# HarmonicControl.net
KiCad netlist of a schematic drawn in Altium Designer
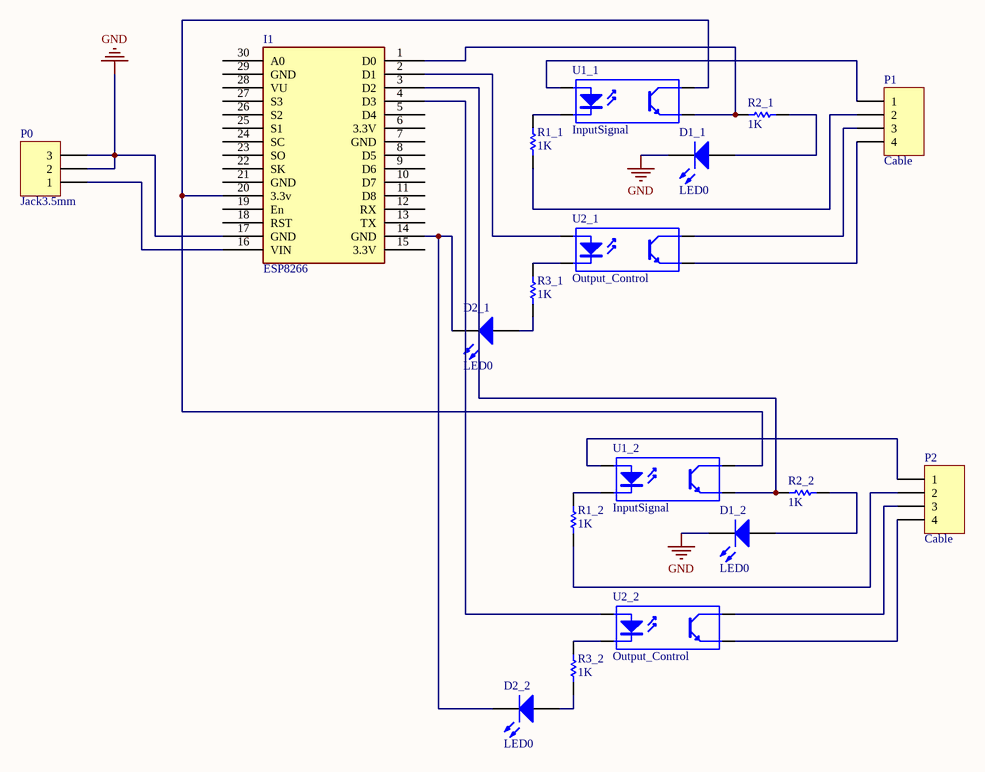
[diagram p0: HarmonicControl.SchDoc]

(export (version "E")
  (design (tool "Eeschema 10.0.6"))
  (components
    (comp (ref "D1_1")
      (value "LED0")
      (footprint "LED-0")
      (description "Typical INFRARED GaAs LED")
      (fields (field (name "PUBLISHER") "Altium Limited"))
      (libsource (lib "Miscellaneous Devices") (part "LED0"))
    )
    (comp (ref "D1_2")
      (value "LED0")
      (footprint "LED-0")
      (description "Typical INFRARED GaAs LED")
      (fields (field (name "PUBLISHER") "Altium Limited"))
      (libsource (lib "Miscellaneous Devices") (part "LED0"))
    )
    (comp (ref "D2_1")
      (value "LED0")
      (footprint "LED-0")
      (description "Typical INFRARED GaAs LED")
      (fields (field (name "PUBLISHER") "Altium Limited"))
      (libsource (lib "Miscellaneous Devices") (part "LED0"))
    )
    (comp (ref "D2_2")
      (value "LED0")
      (footprint "LED-0")
      (description "Typical INFRARED GaAs LED")
      (fields (field (name "PUBLISHER") "Altium Limited"))
      (libsource (lib "Miscellaneous Devices") (part "LED0"))
    )
    (comp (ref "I1")
      (value "ESP8266")
      (footprint "ESP8266_Node_MCU_V3")
      (libsource (lib "ESP8266_NodeMCU_12F_V3") (part "ESP8266_Node_MCU_V3"))
    )
    (comp (ref "P0")
      (value "Jack3.5mm")
      (footprint "HDR1X3")
      (description "Header, 3-Pin")
      (fields (field (name "PUBLISHER") "Altium Limited"))
      (libsource (lib "Miscellaneous Connectors") (part "Header 3"))
    )
    (comp (ref "P1")
      (value "Cable")
      (footprint "HDR1X4")
      (description "Header, 4-Pin")
      (fields (field (name "PUBLISHER") "Altium Limited"))
      (libsource (lib "Miscellaneous Connectors") (part "Header 4"))
    )
    (comp (ref "P2")
      (value "Cable")
      (footprint "HDR1X4")
      (description "Header, 4-Pin")
      (fields (field (name "PUBLISHER") "Altium Limited"))
      (libsource (lib "Miscellaneous Connectors") (part "Header 4"))
    )
    (comp (ref "R1_1")
      (value "1K")
      (footprint "AXIAL-0.3")
      (description "Resistor")
      (fields (field (name "Comment") "Res1") (field (name "PUBLISHER") "Altium Limited"))
      (libsource (lib "Miscellaneous Devices") (part "Res1"))
    )
    (comp (ref "R1_2")
      (value "1K")
      (footprint "AXIAL-0.3")
      (description "Resistor")
      (fields (field (name "Comment") "Res1") (field (name "PUBLISHER") "Altium Limited"))
      (libsource (lib "Miscellaneous Devices") (part "Res1"))
    )
    (comp (ref "R2_1")
      (value "1K")
      (footprint "AXIAL-0.3")
      (description "Resistor")
      (fields (field (name "Comment") "Res1") (field (name "PUBLISHER") "Altium Limited"))
      (libsource (lib "Miscellaneous Devices") (part "Res1"))
    )
    (comp (ref "R2_2")
      (value "1K")
      (footprint "AXIAL-0.3")
      (description "Resistor")
      (fields (field (name "Comment") "Res1") (field (name "PUBLISHER") "Altium Limited"))
      (libsource (lib "Miscellaneous Devices") (part "Res1"))
    )
    (comp (ref "R3_1")
      (value "1K")
      (footprint "AXIAL-0.3")
      (description "Resistor")
      (fields (field (name "Comment") "Res1") (field (name "PUBLISHER") "Altium Limited"))
      (libsource (lib "Miscellaneous Devices") (part "Res1"))
    )
    (comp (ref "R3_2")
      (value "1K")
      (footprint "AXIAL-0.3")
      (description "Resistor")
      (fields (field (name "Comment") "Res1") (field (name "PUBLISHER") "Altium Limited"))
      (libsource (lib "Miscellaneous Devices") (part "Res1"))
    )
    (comp (ref "U1_1")
      (value "InputSignal")
      (footprint "DIP-4")
      (description "4-Pin Phototransistor Optocoupler")
      (fields (field (name "PUBLISHER") "Altium Limited"))
      (libsource (lib "Miscellaneous Devices") (part "Optoisolator1"))
    )
    (comp (ref "U1_2")
      (value "InputSignal")
      (footprint "DIP-4")
      (description "4-Pin Phototransistor Optocoupler")
      (fields (field (name "PUBLISHER") "Altium Limited"))
      (libsource (lib "Miscellaneous Devices") (part "Optoisolator1"))
    )
    (comp (ref "U2_1")
      (value "Output_Control")
      (footprint "DIP-4")
      (description "4-Pin Phototransistor Optocoupler")
      (fields (field (name "PUBLISHER") "Altium Limited"))
      (libsource (lib "Miscellaneous Devices") (part "Optoisolator1"))
    )
    (comp (ref "U2_2")
      (value "Output_Control")
      (footprint "DIP-4")
      (description "4-Pin Phototransistor Optocoupler")
      (fields (field (name "PUBLISHER") "Altium Limited"))
      (libsource (lib "Miscellaneous Devices") (part "Optoisolator1"))
    )
  )
  (nets
    (net (code "1") (name "GND") (class "Default")
      (node (ref "D1_1") (pin "2") (pinfunction "K_2") (pintype "passive"))
      (node (ref "D1_2") (pin "2") (pinfunction "K_2") (pintype "passive"))
      (node (ref "I1") (pin "17") (pinfunction "GND_17") (pintype "passive"))
      (node (ref "P0") (pin "2") (pinfunction "2_2") (pintype "passive"))
      (node (ref "P0") (pin "3") (pinfunction "3_3") (pintype "passive"))
    )
    (net (code "2") (name "Net-(D1_1-A)") (class "Default")
      (node (ref "D1_1") (pin "1") (pinfunction "A_1") (pintype "passive"))
      (node (ref "R2_1") (pin "2") (pinfunction "2_2") (pintype "passive"))
    )
    (net (code "3") (name "Net-(D1_2-A)") (class "Default")
      (node (ref "D1_2") (pin "1") (pinfunction "A_1") (pintype "passive"))
      (node (ref "R2_2") (pin "2") (pinfunction "2_2") (pintype "passive"))
    )
    (net (code "4") (name "Net-(D2_1-A)") (class "Default")
      (node (ref "D2_1") (pin "1") (pinfunction "A_1") (pintype "passive"))
      (node (ref "R3_1") (pin "1") (pinfunction "1_1") (pintype "passive"))
    )
    (net (code "5") (name "Net-(D2_1-K)") (class "Default")
      (node (ref "D2_1") (pin "2") (pinfunction "K_2") (pintype "passive"))
      (node (ref "D2_2") (pin "2") (pinfunction "K_2") (pintype "passive"))
      (node (ref "I1") (pin "14") (pinfunction "GND_14") (pintype "passive"))
    )
    (net (code "6") (name "Net-(D2_2-A)") (class "Default")
      (node (ref "D2_2") (pin "1") (pinfunction "A_1") (pintype "passive"))
      (node (ref "R3_2") (pin "1") (pinfunction "1_1") (pintype "passive"))
    )
    (net (code "7") (name "Net-(I1-3.3v)") (class "Default")
      (node (ref "I1") (pin "20") (pinfunction "3.3v_20") (pintype "passive"))
      (node (ref "U1_1") (pin "4") (pinfunction "C_4") (pintype "passive"))
      (node (ref "U1_2") (pin "4") (pinfunction "C_4") (pintype "passive"))
    )
    (net (code "8") (name "Net-(I1-D0)") (class "Default")
      (node (ref "I1") (pin "1") (pinfunction "D0_1") (pintype "passive"))
      (node (ref "R2_1") (pin "1") (pinfunction "1_1") (pintype "passive"))
      (node (ref "U1_1") (pin "3") (pinfunction "E_3") (pintype "passive"))
    )
    (net (code "9") (name "Net-(I1-D1)") (class "Default")
      (node (ref "I1") (pin "2") (pinfunction "D1_2") (pintype "passive"))
      (node (ref "U2_1") (pin "1") (pinfunction "A_1") (pintype "passive"))
    )
    (net (code "10") (name "Net-(I1-D2)") (class "Default")
      (node (ref "I1") (pin "3") (pinfunction "D2_3") (pintype "passive"))
      (node (ref "R2_2") (pin "1") (pinfunction "1_1") (pintype "passive"))
      (node (ref "U1_2") (pin "3") (pinfunction "E_3") (pintype "passive"))
    )
    (net (code "11") (name "Net-(I1-D3)") (class "Default")
      (node (ref "I1") (pin "4") (pinfunction "D3_4") (pintype "passive"))
      (node (ref "U2_2") (pin "1") (pinfunction "A_1") (pintype "passive"))
    )
    (net (code "12") (name "Net-(I1-VIN)") (class "Default")
      (node (ref "I1") (pin "16") (pinfunction "VIN_16") (pintype "passive"))
      (node (ref "P0") (pin "1") (pinfunction "1_1") (pintype "passive"))
    )
    (net (code "13") (name "Net-(P1-Pad2)") (class "Default")
      (node (ref "P1") (pin "2") (pinfunction "2_2") (pintype "passive"))
      (node (ref "R1_1") (pin "1") (pinfunction "1_1") (pintype "passive"))
    )
    (net (code "14") (name "Net-(P2-Pad2)") (class "Default")
      (node (ref "P2") (pin "2") (pinfunction "2_2") (pintype "passive"))
      (node (ref "R1_2") (pin "1") (pinfunction "1_1") (pintype "passive"))
    )
    (net (code "15") (name "Net-(U1_1-A)") (class "Default")
      (node (ref "P1") (pin "1") (pinfunction "1_1") (pintype "passive"))
      (node (ref "U1_1") (pin "1") (pinfunction "A_1") (pintype "passive"))
    )
    (net (code "16") (name "Net-(U1_1-K)") (class "Default")
      (node (ref "R1_1") (pin "2") (pinfunction "2_2") (pintype "passive"))
      (node (ref "U1_1") (pin "2") (pinfunction "K_2") (pintype "passive"))
    )
    (net (code "17") (name "Net-(U1_2-A)") (class "Default")
      (node (ref "P2") (pin "1") (pinfunction "1_1") (pintype "passive"))
      (node (ref "U1_2") (pin "1") (pinfunction "A_1") (pintype "passive"))
    )
    (net (code "18") (name "Net-(U1_2-K)") (class "Default")
      (node (ref "R1_2") (pin "2") (pinfunction "2_2") (pintype "passive"))
      (node (ref "U1_2") (pin "2") (pinfunction "K_2") (pintype "passive"))
    )
    (net (code "19") (name "Net-(U2_1-C)") (class "Default")
      (node (ref "P1") (pin "3") (pinfunction "3_3") (pintype "passive"))
      (node (ref "U2_1") (pin "4") (pinfunction "C_4") (pintype "passive"))
    )
    (net (code "20") (name "Net-(U2_1-E)") (class "Default")
      (node (ref "P1") (pin "4") (pinfunction "4_4") (pintype "passive"))
      (node (ref "U2_1") (pin "3") (pinfunction "E_3") (pintype "passive"))
    )
    (net (code "21") (name "Net-(U2_1-K)") (class "Default")
      (node (ref "R3_1") (pin "2") (pinfunction "2_2") (pintype "passive"))
      (node (ref "U2_1") (pin "2") (pinfunction "K_2") (pintype "passive"))
    )
    (net (code "22") (name "Net-(U2_2-C)") (class "Default")
      (node (ref "P2") (pin "3") (pinfunction "3_3") (pintype "passive"))
      (node (ref "U2_2") (pin "4") (pinfunction "C_4") (pintype "passive"))
    )
    (net (code "23") (name "Net-(U2_2-E)") (class "Default")
      (node (ref "P2") (pin "4") (pinfunction "4_4") (pintype "passive"))
      (node (ref "U2_2") (pin "3") (pinfunction "E_3") (pintype "passive"))
    )
    (net (code "24") (name "Net-(U2_2-K)") (class "Default")
      (node (ref "R3_2") (pin "2") (pinfunction "2_2") (pintype "passive"))
      (node (ref "U2_2") (pin "2") (pinfunction "K_2") (pintype "passive"))
    )
    (net (code "25") (name "unconnected-(I1-3.3V-Pad6)") (class "Default")
      (node (ref "I1") (pin "6") (pinfunction "3.3V_6") (pintype "passive"))
    )
    (net (code "26") (name "unconnected-(I1-3.3V-Pad15)") (class "Default")
      (node (ref "I1") (pin "15") (pinfunction "3.3V_15") (pintype "passive"))
    )
    (net (code "27") (name "unconnected-(I1-A0-Pad30)") (class "Default")
      (node (ref "I1") (pin "30") (pinfunction "A0_30") (pintype "passive"))
    )
    (net (code "28") (name "unconnected-(I1-D4-Pad5)") (class "Default")
      (node (ref "I1") (pin "5") (pinfunction "D4_5") (pintype "passive"))
    )
    (net (code "29") (name "unconnected-(I1-D5-Pad8)") (class "Default")
      (node (ref "I1") (pin "8") (pinfunction "D5_8") (pintype "passive"))
    )
    (net (code "30") (name "unconnected-(I1-D6-Pad9)") (class "Default")
      (node (ref "I1") (pin "9") (pinfunction "D6_9") (pintype "passive"))
    )
    (net (code "31") (name "unconnected-(I1-D7-Pad10)") (class "Default")
      (node (ref "I1") (pin "10") (pinfunction "D7_10") (pintype "passive"))
    )
    (net (code "32") (name "unconnected-(I1-D8-Pad11)") (class "Default")
      (node (ref "I1") (pin "11") (pinfunction "D8_11") (pintype "passive"))
    )
    (net (code "33") (name "unconnected-(I1-En-Pad19)") (class "Default")
      (node (ref "I1") (pin "19") (pinfunction "En_19") (pintype "passive"))
    )
    (net (code "34") (name "unconnected-(I1-GND-Pad7)") (class "Default")
      (node (ref "I1") (pin "7") (pinfunction "GND_7") (pintype "passive"))
    )
    (net (code "35") (name "unconnected-(I1-GND-Pad21)") (class "Default")
      (node (ref "I1") (pin "21") (pinfunction "GND_21") (pintype "passive"))
    )
    (net (code "36") (name "unconnected-(I1-GND-Pad29)") (class "Default")
      (node (ref "I1") (pin "29") (pinfunction "GND_29") (pintype "passive"))
    )
    (net (code "37") (name "unconnected-(I1-RST-Pad18)") (class "Default")
      (node (ref "I1") (pin "18") (pinfunction "RST_18") (pintype "passive"))
    )
    (net (code "38") (name "unconnected-(I1-RX-Pad12)") (class "Default")
      (node (ref "I1") (pin "12") (pinfunction "RX_12") (pintype "passive"))
    )
    (net (code "39") (name "unconnected-(I1-S1-Pad25)") (class "Default")
      (node (ref "I1") (pin "25") (pinfunction "S1_25") (pintype "passive"))
    )
    (net (code "40") (name "unconnected-(I1-S2-Pad26)") (class "Default")
      (node (ref "I1") (pin "26") (pinfunction "S2_26") (pintype "passive"))
    )
    (net (code "41") (name "unconnected-(I1-S3-Pad27)") (class "Default")
      (node (ref "I1") (pin "27") (pinfunction "S3_27") (pintype "passive"))
    )
    (net (code "42") (name "unconnected-(I1-SC-Pad24)") (class "Default")
      (node (ref "I1") (pin "24") (pinfunction "SC_24") (pintype "passive"))
    )
    (net (code "43") (name "unconnected-(I1-SK-Pad22)") (class "Default")
      (node (ref "I1") (pin "22") (pinfunction "SK_22") (pintype "passive"))
    )
    (net (code "44") (name "unconnected-(I1-SO-Pad23)") (class "Default")
      (node (ref "I1") (pin "23") (pinfunction "SO_23") (pintype "passive"))
    )
    (net (code "45") (name "unconnected-(I1-TX-Pad13)") (class "Default")
      (node (ref "I1") (pin "13") (pinfunction "TX_13") (pintype "passive"))
    )
    (net (code "46") (name "unconnected-(I1-VU-Pad28)") (class "Default")
      (node (ref "I1") (pin "28") (pinfunction "VU_28") (pintype "passive"))
    )
  )
)
